# MCU_v14.net
KiCad netlist of a schematic drawn in EAGLE
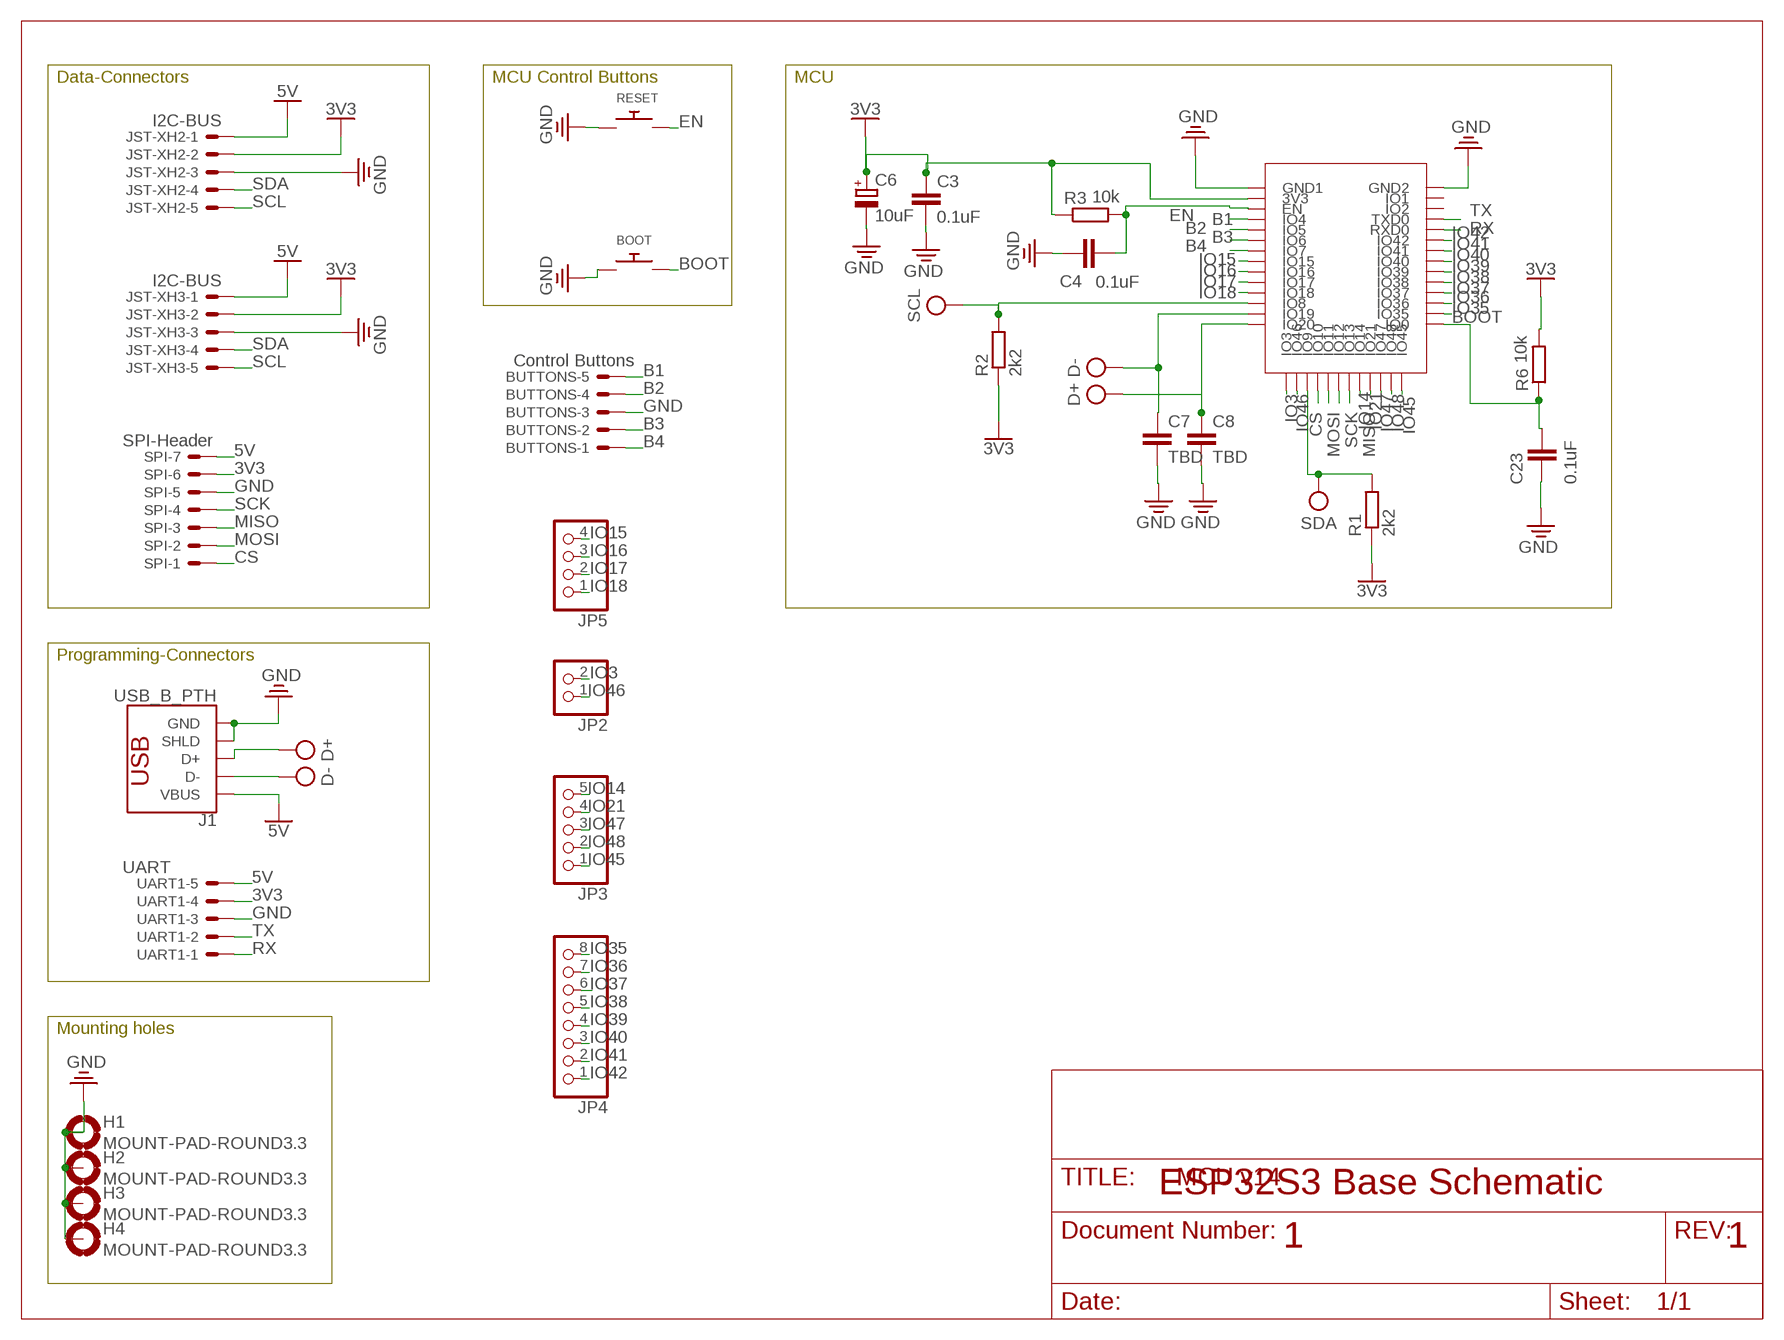
[diagram p0: schematic, sheet 1]

(export (version "E")
  (design (tool "Eeschema 10.0.6"))
  (components
    (comp (ref "BOOT")
      (value "SWITCH_PUSHBUTTONEVQ-PE")
      (footprint "eagle-import:TACT_PANA-EVQ")
      (libsource (lib "eagle-import") (part "SWITCH_PUSHBUTTONEVQ-PE"))
    )
    (comp (ref "BUTTONS")
      (value "Control Buttons")
      (footprint "eagle-import:JST-XH-05-PACKAGE-LONG-PAD")
      (libsource (lib "eagle-import") (part "JST-XH-05-PIN-LONG-PAD"))
    )
    (comp (ref "C3")
      (value "0.1uF")
      (footprint "eagle-import:C025-030X050")
      (libsource (lib "eagle-import") (part "C-EU025-030X050"))
    )
    (comp (ref "C4")
      (value "0.1uF")
      (footprint "eagle-import:C025-030X050")
      (libsource (lib "eagle-import") (part "C-EU025-030X050"))
    )
    (comp (ref "C6")
      (value "10uF")
      (footprint "eagle-import:CAPPRD508W65D1000H1100B")
      (libsource (lib "eagle-import") (part "C-POLRADIAL-11MM-DIA_"))
    )
    (comp (ref "C7")
      (value "TBD")
      (footprint "eagle-import:C025-030X050")
      (libsource (lib "eagle-import") (part "C-EU025-030X050"))
    )
    (comp (ref "C8")
      (value "TBD")
      (footprint "eagle-import:C025-030X050")
      (libsource (lib "eagle-import") (part "C-EU025-030X050"))
    )
    (comp (ref "C23")
      (value "0.1uF")
      (footprint "eagle-import:C025-030X050")
      (libsource (lib "eagle-import") (part "C-EU025-030X050"))
    )
    (comp (ref "H1")
      (value "MOUNT-PAD-ROUND3.3")
      (footprint "eagle-import:3,3-PAD")
      (libsource (lib "eagle-import") (part "MOUNT-PAD-ROUND3.3"))
    )
    (comp (ref "H2")
      (value "MOUNT-PAD-ROUND3.3")
      (footprint "eagle-import:3,3-PAD")
      (libsource (lib "eagle-import") (part "MOUNT-PAD-ROUND3.3"))
    )
    (comp (ref "H3")
      (value "MOUNT-PAD-ROUND3.3")
      (footprint "eagle-import:3,3-PAD")
      (libsource (lib "eagle-import") (part "MOUNT-PAD-ROUND3.3"))
    )
    (comp (ref "H4")
      (value "MOUNT-PAD-ROUND3.3")
      (footprint "eagle-import:3,3-PAD")
      (libsource (lib "eagle-import") (part "MOUNT-PAD-ROUND3.3"))
    )
    (comp (ref "J1")
      (value "USB_B_PTH")
      (footprint "eagle-import:USB-B-PTH")
      (libsource (lib "eagle-import") (part "USB_B_PTH"))
    )
    (comp (ref "JP2")
      (value "PINHD-1X2")
      (footprint "eagle-import:1X02")
      (libsource (lib "eagle-import") (part "PINHD-1X2"))
    )
    (comp (ref "JP3")
      (value "PINHD-1X55X2MM")
      (footprint "eagle-import:1_05X2MM")
      (libsource (lib "eagle-import") (part "PINHD-1X55X2MM"))
    )
    (comp (ref "JP4")
      (value "PINHD-1X8")
      (footprint "eagle-import:1X08")
      (libsource (lib "eagle-import") (part "PINHD-1X8"))
    )
    (comp (ref "JP5")
      (value "PINHD-1X4")
      (footprint "eagle-import:1X04")
      (libsource (lib "eagle-import") (part "PINHD-1X4"))
    )
    (comp (ref "JST-XH2")
      (value "I2C-BUS")
      (footprint "eagle-import:JST-XH-05-PACKAGE-LONG-PAD")
      (libsource (lib "eagle-import") (part "JST-XH-05-PIN-LONG-PAD"))
    )
    (comp (ref "JST-XH3")
      (value "I2C-BUS")
      (footprint "eagle-import:JST-XH-05-PACKAGE-LONG-PAD")
      (libsource (lib "eagle-import") (part "JST-XH-05-PIN-LONG-PAD"))
    )
    (comp (ref "R1")
      (value "2k2")
      (footprint "eagle-import:0204_5")
      (libsource (lib "eagle-import") (part "R-EU_0204/5"))
    )
    (comp (ref "R2")
      (value "2k2")
      (footprint "eagle-import:0204_5")
      (libsource (lib "eagle-import") (part "R-EU_0204/5"))
    )
    (comp (ref "R3")
      (value "10k")
      (footprint "eagle-import:0204_7")
      (libsource (lib "eagle-import") (part "R-EU_0204/7"))
    )
    (comp (ref "R6")
      (value "10k")
      (footprint "eagle-import:0204_7")
      (libsource (lib "eagle-import") (part "R-EU_0204/7"))
    )
    (comp (ref "RESET")
      (value "SWITCH_PUSHBUTTONEVQ-PE")
      (footprint "eagle-import:TACT_PANA-EVQ")
      (libsource (lib "eagle-import") (part "SWITCH_PUSHBUTTONEVQ-PE"))
    )
    (comp (ref "SPI")
      (value "SPI-Header")
      (footprint "eagle-import:JST-XH-07-PACKAGE-LONG-PAD")
      (libsource (lib "eagle-import") (part "JST-XH-07-PIN-LONG-PAD"))
    )
    (comp (ref "U$1")
      (value "ESP32-S3-WROOM-1")
      (footprint "eagle-import:ESP32-S3-WROOM-1")
      (libsource (lib "eagle-import") (part "ESP32-S3-WROOM-1"))
    )
    (comp (ref "UART1")
      (value "UART")
      (footprint "eagle-import:JST-XH-05-PACKAGE-ROUND-PAD")
      (libsource (lib "eagle-import") (part "JST-XH-05-PIN-ROUND-PAD"))
    )
  )
  (nets
    (net (code "1") (name "/B1") (class "Default")
      (node (ref "BUTTONS") (pin "5") (pinfunction "S_5") (pintype "passive"))
      (node (ref "U$1") (pin "IO4") (pinfunction "IO4_IO4") (pintype "bidirectional"))
    )
    (net (code "2") (name "/B2") (class "Default")
      (node (ref "BUTTONS") (pin "4") (pinfunction "S_4") (pintype "passive"))
      (node (ref "U$1") (pin "IO5") (pinfunction "IO5_IO5") (pintype "bidirectional"))
    )
    (net (code "3") (name "/B3") (class "Default")
      (node (ref "BUTTONS") (pin "2") (pinfunction "S_2") (pintype "passive"))
      (node (ref "U$1") (pin "IO6") (pinfunction "IO6_IO6") (pintype "bidirectional"))
    )
    (net (code "4") (name "/B4") (class "Default")
      (node (ref "BUTTONS") (pin "1") (pinfunction "S_1") (pintype "passive"))
      (node (ref "U$1") (pin "IO7") (pinfunction "IO7_IO7") (pintype "bidirectional"))
    )
    (net (code "5") (name "/BOOT") (class "Default")
      (node (ref "BOOT") (pin "P$2") (pinfunction "P$2_P$2") (pintype "passive"))
      (node (ref "C23") (pin "2") (pinfunction "2_2") (pintype "passive"))
      (node (ref "R6") (pin "1") (pinfunction "1_1") (pintype "passive"))
      (node (ref "U$1") (pin "IO0") (pinfunction "IO0_IO0") (pintype "bidirectional"))
    )
    (net (code "6") (name "/CS") (class "Default")
      (node (ref "SPI") (pin "1") (pinfunction "S_1") (pintype "passive"))
      (node (ref "U$1") (pin "IO10") (pinfunction "IO10_IO10") (pintype "bidirectional"))
    )
    (net (code "7") (name "/EN") (class "Default")
      (node (ref "C4") (pin "2") (pinfunction "2_2") (pintype "passive"))
      (node (ref "R3") (pin "2") (pinfunction "2_2") (pintype "passive"))
      (node (ref "RESET") (pin "P$2") (pinfunction "P$2_P$2") (pintype "passive"))
      (node (ref "U$1") (pin "EN") (pinfunction "EN_EN") (pintype "bidirectional"))
    )
    (net (code "8") (name "/IO3") (class "Default")
      (node (ref "JP2") (pin "2") (pinfunction "2_2") (pintype "passive"))
      (node (ref "U$1") (pin "IO3") (pinfunction "IO3_IO3") (pintype "bidirectional"))
    )
    (net (code "9") (name "/IO14") (class "Default")
      (node (ref "JP3") (pin "5") (pinfunction "5_5") (pintype "passive"))
      (node (ref "U$1") (pin "IO14") (pinfunction "IO14_IO14") (pintype "bidirectional"))
    )
    (net (code "10") (name "/IO15") (class "Default")
      (node (ref "JP5") (pin "4") (pinfunction "4_4") (pintype "passive"))
      (node (ref "U$1") (pin "IO15") (pinfunction "IO15_IO15") (pintype "bidirectional"))
    )
    (net (code "11") (name "/IO16") (class "Default")
      (node (ref "JP5") (pin "3") (pinfunction "3_3") (pintype "passive"))
      (node (ref "U$1") (pin "IO16") (pinfunction "IO16_IO16") (pintype "bidirectional"))
    )
    (net (code "12") (name "/IO17") (class "Default")
      (node (ref "JP5") (pin "2") (pinfunction "2_2") (pintype "passive"))
      (node (ref "U$1") (pin "IO17") (pinfunction "IO17_IO17") (pintype "bidirectional"))
    )
    (net (code "13") (name "/IO18") (class "Default")
      (node (ref "JP5") (pin "1") (pinfunction "1_1") (pintype "passive"))
      (node (ref "U$1") (pin "IO18") (pinfunction "IO18_IO18") (pintype "bidirectional"))
    )
    (net (code "14") (name "/IO21") (class "Default")
      (node (ref "JP3") (pin "4") (pinfunction "4_4") (pintype "passive"))
      (node (ref "U$1") (pin "IO21") (pinfunction "IO21_IO21") (pintype "bidirectional"))
    )
    (net (code "15") (name "/IO35") (class "Default")
      (node (ref "JP4") (pin "8") (pinfunction "8_8") (pintype "passive"))
      (node (ref "U$1") (pin "IO35") (pinfunction "IO35_IO35") (pintype "bidirectional"))
    )
    (net (code "16") (name "/IO36") (class "Default")
      (node (ref "JP4") (pin "7") (pinfunction "7_7") (pintype "passive"))
      (node (ref "U$1") (pin "IO36") (pinfunction "IO36_IO36") (pintype "bidirectional"))
    )
    (net (code "17") (name "/IO37") (class "Default")
      (node (ref "JP4") (pin "6") (pinfunction "6_6") (pintype "passive"))
      (node (ref "U$1") (pin "IO37") (pinfunction "IO37_IO37") (pintype "bidirectional"))
    )
    (net (code "18") (name "/IO38") (class "Default")
      (node (ref "JP4") (pin "5") (pinfunction "5_5") (pintype "passive"))
      (node (ref "U$1") (pin "IO38") (pinfunction "IO38_IO38") (pintype "bidirectional"))
    )
    (net (code "19") (name "/IO39") (class "Default")
      (node (ref "JP4") (pin "4") (pinfunction "4_4") (pintype "passive"))
      (node (ref "U$1") (pin "IO39") (pinfunction "IO39_IO39") (pintype "bidirectional"))
    )
    (net (code "20") (name "/IO40") (class "Default")
      (node (ref "JP4") (pin "3") (pinfunction "3_3") (pintype "passive"))
      (node (ref "U$1") (pin "IO40") (pinfunction "IO40_IO40") (pintype "bidirectional"))
    )
    (net (code "21") (name "/IO41") (class "Default")
      (node (ref "JP4") (pin "2") (pinfunction "2_2") (pintype "passive"))
      (node (ref "U$1") (pin "IO41") (pinfunction "IO41_IO41") (pintype "bidirectional"))
    )
    (net (code "22") (name "/IO42") (class "Default")
      (node (ref "JP4") (pin "1") (pinfunction "1_1") (pintype "passive"))
      (node (ref "U$1") (pin "IO42") (pinfunction "IO42_IO42") (pintype "bidirectional"))
    )
    (net (code "23") (name "/IO45") (class "Default")
      (node (ref "JP3") (pin "1") (pinfunction "1_1") (pintype "passive"))
      (node (ref "U$1") (pin "IO45") (pinfunction "IO45_IO45") (pintype "bidirectional"))
    )
    (net (code "24") (name "/IO46") (class "Default")
      (node (ref "JP2") (pin "1") (pinfunction "1_1") (pintype "passive"))
      (node (ref "U$1") (pin "IO46") (pinfunction "IO46_IO46") (pintype "bidirectional"))
    )
    (net (code "25") (name "/IO47") (class "Default")
      (node (ref "JP3") (pin "3") (pinfunction "3_3") (pintype "passive"))
      (node (ref "U$1") (pin "IO47") (pinfunction "IO47_IO47") (pintype "bidirectional"))
    )
    (net (code "26") (name "/IO48") (class "Default")
      (node (ref "JP3") (pin "2") (pinfunction "2_2") (pintype "passive"))
      (node (ref "U$1") (pin "IO48") (pinfunction "IO48_IO48") (pintype "bidirectional"))
    )
    (net (code "27") (name "/MISO") (class "Default")
      (node (ref "SPI") (pin "3") (pinfunction "S_3") (pintype "passive"))
      (node (ref "U$1") (pin "IO13") (pinfunction "IO13_IO13") (pintype "bidirectional"))
    )
    (net (code "28") (name "/MOSI") (class "Default")
      (node (ref "SPI") (pin "2") (pinfunction "S_2") (pintype "passive"))
      (node (ref "U$1") (pin "IO11") (pinfunction "IO11_IO11") (pintype "bidirectional"))
    )
    (net (code "29") (name "/RX") (class "Default")
      (node (ref "U$1") (pin "RXD0") (pinfunction "RXD0_RXD0") (pintype "bidirectional"))
      (node (ref "UART1") (pin "1") (pinfunction "S_1") (pintype "passive"))
    )
    (net (code "30") (name "/SCK") (class "Default")
      (node (ref "SPI") (pin "4") (pinfunction "S_4") (pintype "passive"))
      (node (ref "U$1") (pin "IO12") (pinfunction "IO12_IO12") (pintype "bidirectional"))
    )
    (net (code "31") (name "/TX") (class "Default")
      (node (ref "U$1") (pin "TXD0") (pinfunction "TXD0_TXD0") (pintype "bidirectional"))
      (node (ref "UART1") (pin "2") (pinfunction "S_2") (pintype "passive"))
    )
    (net (code "32") (name "3V3") (class "Default")
      (node (ref "C3") (pin "1") (pinfunction "1_1") (pintype "passive"))
      (node (ref "C6") (pin "1") (pinfunction "+_1") (pintype "passive"))
      (node (ref "JST-XH2") (pin "2") (pinfunction "S_2") (pintype "passive"))
      (node (ref "JST-XH3") (pin "2") (pinfunction "S_2") (pintype "passive"))
      (node (ref "R1") (pin "1") (pinfunction "1_1") (pintype "passive"))
      (node (ref "R2") (pin "1") (pinfunction "1_1") (pintype "passive"))
      (node (ref "R3") (pin "1") (pinfunction "1_1") (pintype "passive"))
      (node (ref "R6") (pin "2") (pinfunction "2_2") (pintype "passive"))
      (node (ref "SPI") (pin "6") (pinfunction "S_6") (pintype "passive"))
      (node (ref "U$1") (pin "3V3") (pinfunction "3V3_3V3") (pintype "bidirectional"))
      (node (ref "UART1") (pin "4") (pinfunction "S_4") (pintype "passive"))
    )
    (net (code "33") (name "5V") (class "Default")
      (node (ref "J1") (pin "VBUS") (pinfunction "VBUS_VBUS") (pintype "power_in"))
      (node (ref "JST-XH2") (pin "1") (pinfunction "S_1") (pintype "passive"))
      (node (ref "JST-XH3") (pin "1") (pinfunction "S_1") (pintype "passive"))
      (node (ref "SPI") (pin "7") (pinfunction "S_7") (pintype "passive"))
      (node (ref "UART1") (pin "5") (pinfunction "S_5") (pintype "passive"))
    )
    (net (code "34") (name "D+") (class "Default")
      (node (ref "C8") (pin "1") (pinfunction "1_1") (pintype "passive"))
      (node (ref "J1") (pin "D+") (pinfunction "D+_D+") (pintype "bidirectional"))
      (node (ref "U$1") (pin "IO20") (pinfunction "IO20_IO20") (pintype "bidirectional"))
    )
    (net (code "35") (name "D-") (class "Default")
      (node (ref "C7") (pin "1") (pinfunction "1_1") (pintype "passive"))
      (node (ref "J1") (pin "D-") (pinfunction "D-_D-") (pintype "bidirectional"))
      (node (ref "U$1") (pin "IO19") (pinfunction "IO19_IO19") (pintype "bidirectional"))
    )
    (net (code "36") (name "GND") (class "Default")
      (node (ref "BOOT") (pin "P$1") (pinfunction "P$1_P$1") (pintype "passive"))
      (node (ref "BUTTONS") (pin "3") (pinfunction "S_3") (pintype "passive"))
      (node (ref "C23") (pin "1") (pinfunction "1_1") (pintype "passive"))
      (node (ref "C3") (pin "2") (pinfunction "2_2") (pintype "passive"))
      (node (ref "C4") (pin "1") (pinfunction "1_1") (pintype "passive"))
      (node (ref "C6") (pin "2") (pinfunction "-_2") (pintype "passive"))
      (node (ref "C7") (pin "2") (pinfunction "2_2") (pintype "passive"))
      (node (ref "C8") (pin "2") (pinfunction "2_2") (pintype "passive"))
      (node (ref "H1") (pin "B3,3") (pinfunction "MOUNT_B3,3") (pintype "passive"))
      (node (ref "H2") (pin "B3,3") (pinfunction "MOUNT_B3,3") (pintype "passive"))
      (node (ref "H3") (pin "B3,3") (pinfunction "MOUNT_B3,3") (pintype "passive"))
      (node (ref "H4") (pin "B3,3") (pinfunction "MOUNT_B3,3") (pintype "passive"))
      (node (ref "J1") (pin "GND") (pinfunction "GND_GND") (pintype "power_in"))
      (node (ref "J1") (pin "SHLD1") (pinfunction "SHLD_SHLD1") (pintype "bidirectional"))
      (node (ref "J1") (pin "SHLD2") (pinfunction "SHLD_SHLD2") (pintype "bidirectional"))
      (node (ref "JST-XH2") (pin "3") (pinfunction "S_3") (pintype "passive"))
      (node (ref "JST-XH3") (pin "3") (pinfunction "S_3") (pintype "passive"))
      (node (ref "RESET") (pin "P$1") (pinfunction "P$1_P$1") (pintype "passive"))
      (node (ref "SPI") (pin "5") (pinfunction "S_5") (pintype "passive"))
      (node (ref "U$1") (pin "GND1") (pinfunction "GND1_GND1") (pintype "bidirectional"))
      (node (ref "U$1") (pin "GND2") (pinfunction "GND2_GND2") (pintype "bidirectional"))
      (node (ref "UART1") (pin "3") (pinfunction "S_3") (pintype "passive"))
    )
    (net (code "37") (name "SCL") (class "Default")
      (node (ref "JST-XH2") (pin "5") (pinfunction "S_5") (pintype "passive"))
      (node (ref "JST-XH3") (pin "5") (pinfunction "S_5") (pintype "passive"))
      (node (ref "R2") (pin "2") (pinfunction "2_2") (pintype "passive"))
      (node (ref "U$1") (pin "IO8") (pinfunction "IO8_IO8") (pintype "bidirectional"))
    )
    (net (code "38") (name "SDA") (class "Default")
      (node (ref "JST-XH2") (pin "4") (pinfunction "S_4") (pintype "passive"))
      (node (ref "JST-XH3") (pin "4") (pinfunction "S_4") (pintype "passive"))
      (node (ref "R1") (pin "2") (pinfunction "2_2") (pintype "passive"))
      (node (ref "U$1") (pin "IO9") (pinfunction "IO9_IO9") (pintype "bidirectional"))
    )
    (net (code "39") (name "unconnected-(U$1-PadIO1)") (class "Default")
      (node (ref "U$1") (pin "IO1") (pinfunction "IO1_IO1") (pintype "bidirectional"))
    )
    (net (code "40") (name "unconnected-(U$1-PadIO2)") (class "Default")
      (node (ref "U$1") (pin "IO2") (pinfunction "IO2_IO2") (pintype "bidirectional"))
    )
  )
)
